# cyberspace-1-cpu-card.net
KiCad netlist of a schematic drawn in EAGLE
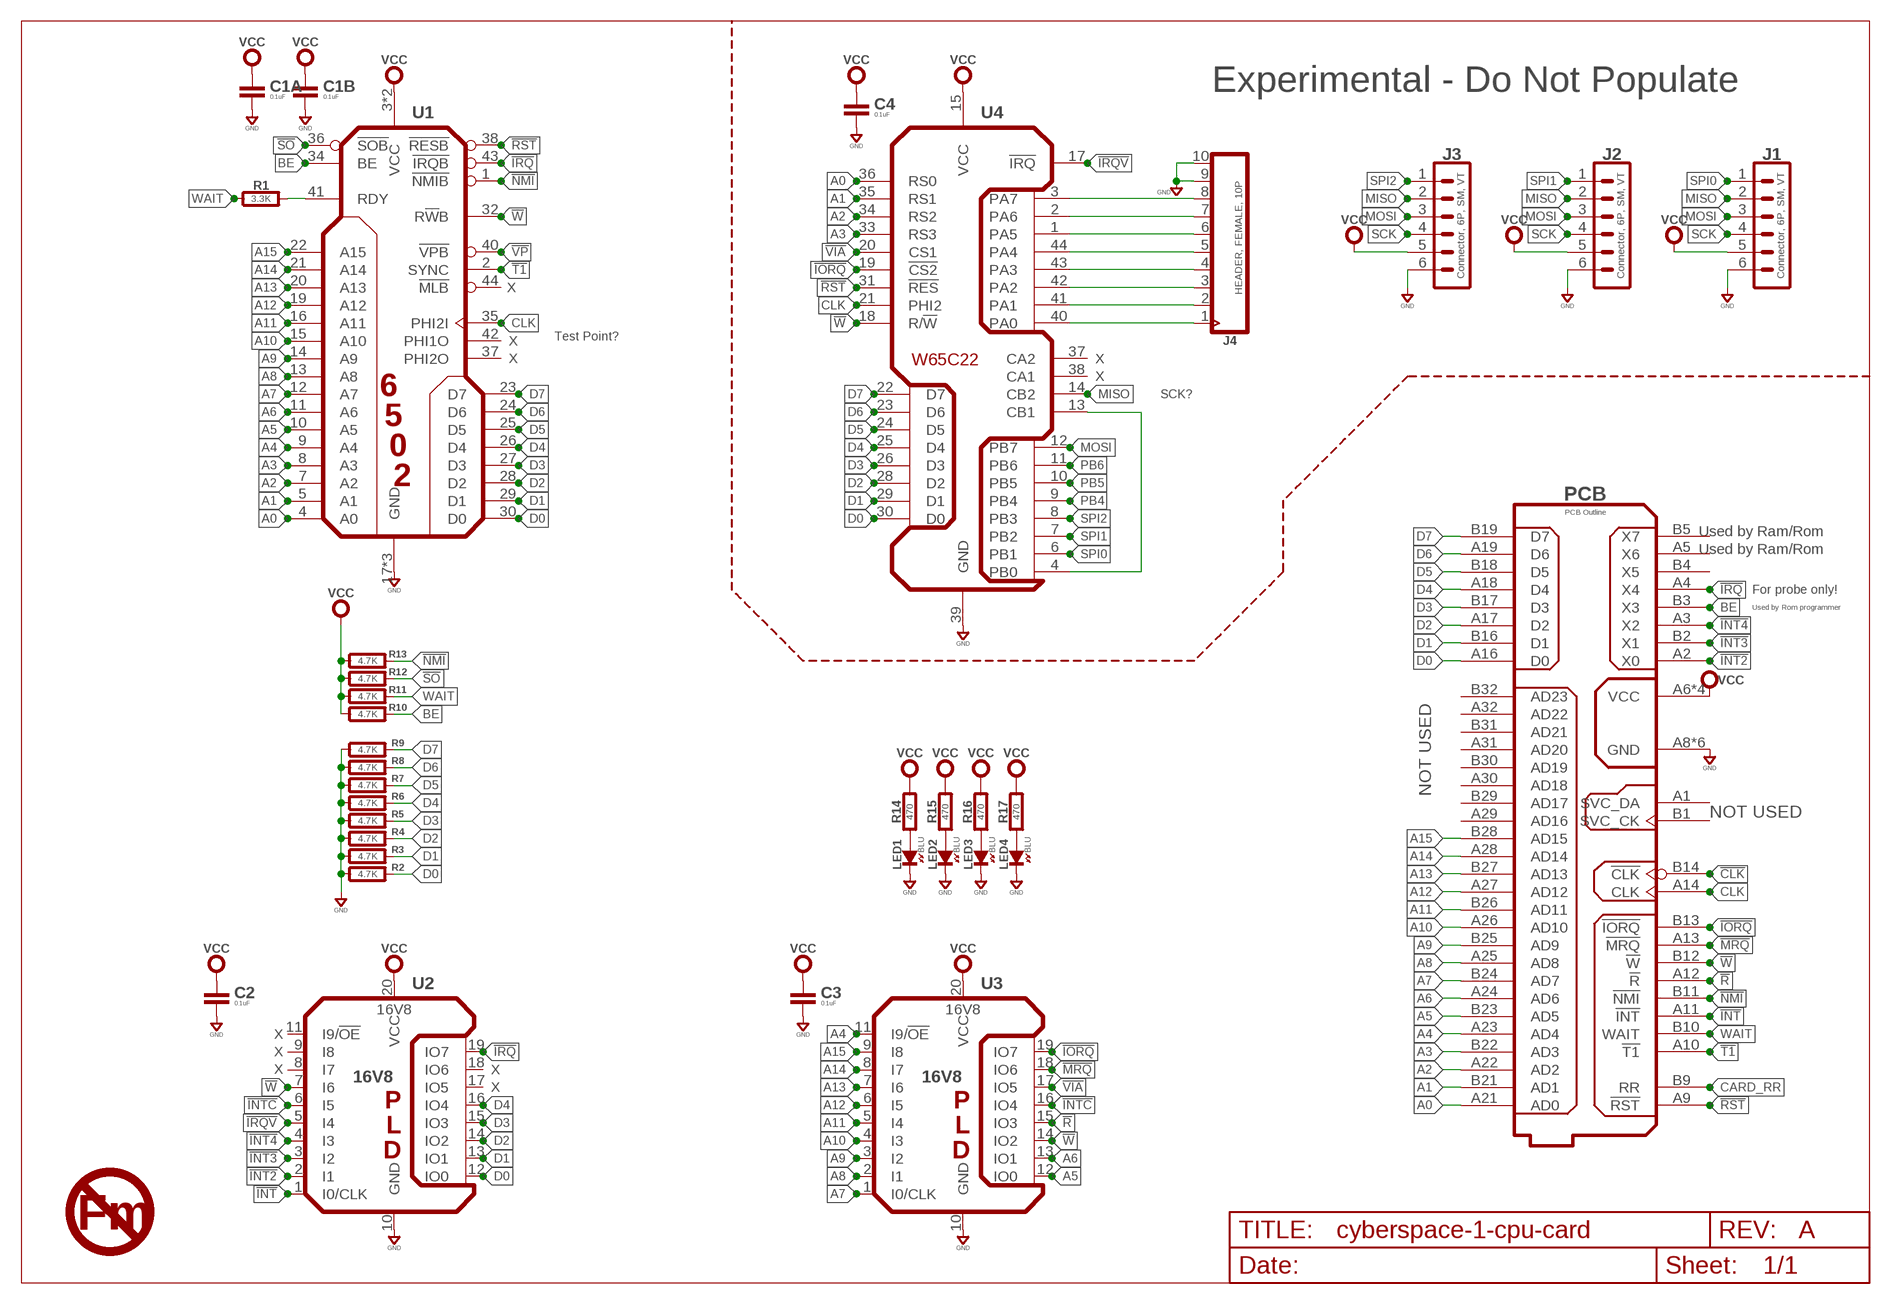
[diagram p0: schematic, sheet 1]

(export (version "E")
  (design (tool "Eeschema 10.0.6"))
  (components
    (comp (ref "C1A")
      (value "0.1uF")
      (footprint "eagle-import:0603-CAP")
      (libsource (lib "eagle-import") (part "CAPACITOR0603"))
    )
    (comp (ref "C1B")
      (value "0.1uF")
      (footprint "eagle-import:0603-CAP")
      (libsource (lib "eagle-import") (part "CAPACITOR0603"))
    )
    (comp (ref "C2")
      (value "0.1uF")
      (footprint "eagle-import:0603-CAP")
      (libsource (lib "eagle-import") (part "CAPACITOR0603"))
    )
    (comp (ref "C3")
      (value "0.1uF")
      (footprint "eagle-import:0603-CAP")
      (libsource (lib "eagle-import") (part "CAPACITOR0603"))
    )
    (comp (ref "C4")
      (value "0.1uF")
      (footprint "eagle-import:0603-CAP")
      (libsource (lib "eagle-import") (part "CAPACITOR0603"))
    )
    (comp (ref "J1")
      (value "Connector, 6P, SM, VT")
      (footprint "eagle-import:BM06B-SRSS-TB")
      (fields (field (name "MFR") "JST") (field (name "MPN") "BM06-SRSS-TB"))
      (libsource (lib "eagle-import") (part "06P-SM-VT-SMT"))
    )
    (comp (ref "J2")
      (value "Connector, 6P, SM, VT")
      (footprint "eagle-import:BM06B-SRSS-TB")
      (fields (field (name "MFR") "JST") (field (name "MPN") "BM06-SRSS-TB"))
      (libsource (lib "eagle-import") (part "06P-SM-VT-SMT"))
    )
    (comp (ref "J3")
      (value "Connector, 6P, SM, VT")
      (footprint "eagle-import:BM06B-SRSS-TB")
      (fields (field (name "MFR") "JST") (field (name "MPN") "BM06-SRSS-TB"))
      (libsource (lib "eagle-import") (part "06P-SM-VT-SMT"))
    )
    (comp (ref "J4")
      (value "HEADER, FEMALE, 10P")
      (footprint "eagle-import:H10-2.54")
      (fields (field (name "MFR") "Tayda") (field (name "MPN") "A-1306"))
      (libsource (lib "eagle-import") (part "CON_10X1-VT-THD-FEMALE"))
    )
    (comp (ref "LED1")
      (value "BLU")
      (footprint "eagle-import:SMD_0603")
      (libsource (lib "eagle-import") (part "SMT0603"))
    )
    (comp (ref "LED2")
      (value "BLU")
      (footprint "eagle-import:SMD_0603")
      (libsource (lib "eagle-import") (part "SMT0603"))
    )
    (comp (ref "LED3")
      (value "BLU")
      (footprint "eagle-import:SMD_0603")
      (libsource (lib "eagle-import") (part "SMT0603"))
    )
    (comp (ref "LED4")
      (value "BLU")
      (footprint "eagle-import:SMD_0603")
      (libsource (lib "eagle-import") (part "SMT0603"))
    )
    (comp (ref "PCB")
      (value "PCB Outline")
      (footprint "eagle-import:CYBERSPACE-CARD-TYPE-1A")
      (libsource (lib "eagle-import") (part "CYBERSPACE-1-CARD-1A"))
    )
    (comp (ref "R1")
      (value "3.3K")
      (footprint "eagle-import:0603-RES")
      (libsource (lib "eagle-import") (part "RESISTOR0603"))
    )
    (comp (ref "R2")
      (value "4.7K")
      (footprint "eagle-import:0603-RES")
      (libsource (lib "eagle-import") (part "RESISTOR0603"))
    )
    (comp (ref "R3")
      (value "4.7K")
      (footprint "eagle-import:0603-RES")
      (libsource (lib "eagle-import") (part "RESISTOR0603"))
    )
    (comp (ref "R4")
      (value "4.7K")
      (footprint "eagle-import:0603-RES")
      (libsource (lib "eagle-import") (part "RESISTOR0603"))
    )
    (comp (ref "R5")
      (value "4.7K")
      (footprint "eagle-import:0603-RES")
      (libsource (lib "eagle-import") (part "RESISTOR0603"))
    )
    (comp (ref "R6")
      (value "4.7K")
      (footprint "eagle-import:0603-RES")
      (libsource (lib "eagle-import") (part "RESISTOR0603"))
    )
    (comp (ref "R7")
      (value "4.7K")
      (footprint "eagle-import:0603-RES")
      (libsource (lib "eagle-import") (part "RESISTOR0603"))
    )
    (comp (ref "R8")
      (value "4.7K")
      (footprint "eagle-import:0603-RES")
      (libsource (lib "eagle-import") (part "RESISTOR0603"))
    )
    (comp (ref "R9")
      (value "4.7K")
      (footprint "eagle-import:0603-RES")
      (libsource (lib "eagle-import") (part "RESISTOR0603"))
    )
    (comp (ref "R10")
      (value "4.7K")
      (footprint "eagle-import:0603-RES")
      (libsource (lib "eagle-import") (part "RESISTOR0603"))
    )
    (comp (ref "R11")
      (value "4.7K")
      (footprint "eagle-import:0603-RES")
      (libsource (lib "eagle-import") (part "RESISTOR0603"))
    )
    (comp (ref "R12")
      (value "4.7K")
      (footprint "eagle-import:0603-RES")
      (libsource (lib "eagle-import") (part "RESISTOR0603"))
    )
    (comp (ref "R13")
      (value "4.7K")
      (footprint "eagle-import:0603-RES")
      (libsource (lib "eagle-import") (part "RESISTOR0603"))
    )
    (comp (ref "R14")
      (value "470")
      (footprint "eagle-import:0603-RES")
      (libsource (lib "eagle-import") (part "RESISTOR0603"))
    )
    (comp (ref "R15")
      (value "470")
      (footprint "eagle-import:0603-RES")
      (libsource (lib "eagle-import") (part "RESISTOR0603"))
    )
    (comp (ref "R16")
      (value "470")
      (footprint "eagle-import:0603-RES")
      (libsource (lib "eagle-import") (part "RESISTOR0603"))
    )
    (comp (ref "R17")
      (value "470")
      (footprint "eagle-import:0603-RES")
      (libsource (lib "eagle-import") (part "RESISTOR0603"))
    )
    (comp (ref "U$2")
      (value "NO-FERMIUM-5MM")
      (footprint "eagle-import:NO-FERMIUM-5MM")
      (libsource (lib "eagle-import") (part "NO-FERMIUM-5MM"))
    )
    (comp (ref "U1")
      (value "6502 Processor")
      (footprint "eagle-import:TQFP-44-10")
      (fields (field (name "MFR") "WDC") (field (name "MPN") "W65C02S6TQG-14"))
      (libsource (lib "eagle-import") (part "6502S?QC"))
    )
    (comp (ref "U2")
      (value "16V8")
      (footprint "eagle-import:SOP20")
      (fields (field (name "MFR") "Atmel") (field (name "MPN") "AF16V8B15SU"))
      (libsource (lib "eagle-import") (part "16V8-SOIC"))
    )
    (comp (ref "U3")
      (value "16V8")
      (footprint "eagle-import:SOP20")
      (fields (field (name "MFR") "Atmel") (field (name "MPN") "AF16V8B15SU"))
      (libsource (lib "eagle-import") (part "16V8-SOIC"))
    )
    (comp (ref "U4")
      (value "W65C22")
      (footprint "eagle-import:TQFP-44-10")
      (fields (field (name "MFR") "WDC") (field (name "MPN") "W65C22S6TQG-14"))
      (libsource (lib "eagle-import") (part "6522?QC"))
    )
  )
  (nets
    (net (code "1") (name "/~{CLK}") (class "Default")
      (node (ref "PCB") (pin "B14") (pinfunction "~{CLK}_B14") (pintype "bidirectional"))
    )
    (net (code "2") (name "/~{INT2}") (class "Default")
      (node (ref "PCB") (pin "A2") (pinfunction "X0_A2") (pintype "bidirectional"))
      (node (ref "U2") (pin "2") (pinfunction "I1_2") (pintype "bidirectional"))
    )
    (net (code "3") (name "/~{INT3}") (class "Default")
      (node (ref "PCB") (pin "B2") (pinfunction "X1_B2") (pintype "bidirectional"))
      (node (ref "U2") (pin "3") (pinfunction "I2_3") (pintype "bidirectional"))
    )
    (net (code "4") (name "/~{INT4}") (class "Default")
      (node (ref "PCB") (pin "A3") (pinfunction "X2_A3") (pintype "bidirectional"))
      (node (ref "U2") (pin "4") (pinfunction "I3_4") (pintype "bidirectional"))
    )
    (net (code "5") (name "/~{INTC}") (class "Default")
      (node (ref "U2") (pin "6") (pinfunction "I5_6") (pintype "bidirectional"))
      (node (ref "U3") (pin "16") (pinfunction "IO4_16") (pintype "bidirectional"))
    )
    (net (code "6") (name "/~{INT}") (class "Default")
      (node (ref "PCB") (pin "A11") (pinfunction "~{INT}_A11") (pintype "bidirectional"))
      (node (ref "U2") (pin "1") (pinfunction "I0/CLK_1") (pintype "bidirectional"))
    )
    (net (code "7") (name "/~{IORQ}") (class "Default")
      (node (ref "PCB") (pin "B13") (pinfunction "~{IORQ}_B13") (pintype "bidirectional"))
      (node (ref "U3") (pin "19") (pinfunction "IO7_19") (pintype "bidirectional"))
      (node (ref "U4") (pin "19") (pinfunction "~{CS2}_19") (pintype "input"))
    )
    (net (code "8") (name "/~{IRQV}") (class "Default")
      (node (ref "U2") (pin "5") (pinfunction "I4_5") (pintype "bidirectional"))
      (node (ref "U4") (pin "17") (pinfunction "~{IRQ}_17") (pintype "output"))
    )
    (net (code "9") (name "/~{IRQ}") (class "Default")
      (node (ref "PCB") (pin "A4") (pinfunction "X4_A4") (pintype "bidirectional"))
      (node (ref "U1") (pin "43") (pinfunction "~{IRQB}_43") (pintype "input"))
      (node (ref "U2") (pin "19") (pinfunction "IO7_19") (pintype "bidirectional"))
    )
    (net (code "10") (name "/~{MRQ}") (class "Default")
      (node (ref "PCB") (pin "A13") (pinfunction "~{MRQ}_A13") (pintype "bidirectional"))
      (node (ref "U3") (pin "18") (pinfunction "IO6_18") (pintype "bidirectional"))
    )
    (net (code "11") (name "/~{NMI}") (class "Default")
      (node (ref "PCB") (pin "B11") (pinfunction "~{NMI}_B11") (pintype "bidirectional"))
      (node (ref "R13") (pin "2") (pinfunction "2_2") (pintype "passive"))
      (node (ref "U1") (pin "1") (pinfunction "~{NMIB}_1") (pintype "input"))
    )
    (net (code "12") (name "/~{RST}") (class "Default")
      (node (ref "PCB") (pin "A9") (pinfunction "~{RST}_A9") (pintype "bidirectional"))
      (node (ref "U1") (pin "38") (pinfunction "~{RESB}_38") (pintype "input"))
      (node (ref "U4") (pin "31") (pinfunction "~{RES}_31") (pintype "input"))
    )
    (net (code "13") (name "/~{R}") (class "Default")
      (node (ref "PCB") (pin "A12") (pinfunction "~{R}_A12") (pintype "bidirectional"))
      (node (ref "U3") (pin "15") (pinfunction "IO3_15") (pintype "bidirectional"))
    )
    (net (code "14") (name "/~{SO}") (class "Default")
      (node (ref "R12") (pin "2") (pinfunction "2_2") (pintype "passive"))
      (node (ref "U1") (pin "36") (pinfunction "~{SOB}_36") (pintype "input"))
    )
    (net (code "15") (name "/~{T1}") (class "Default")
      (node (ref "PCB") (pin "A10") (pinfunction "~{T1}_A10") (pintype "bidirectional"))
      (node (ref "U1") (pin "2") (pinfunction "SYNC_2") (pintype "output"))
    )
    (net (code "16") (name "/~{VIA}") (class "Default")
      (node (ref "U3") (pin "17") (pinfunction "IO5_17") (pintype "bidirectional"))
      (node (ref "U4") (pin "20") (pinfunction "CS1_20") (pintype "input"))
    )
    (net (code "17") (name "/~{VP}") (class "Default")
      (node (ref "U1") (pin "40") (pinfunction "~{VPB}_40") (pintype "output"))
    )
    (net (code "18") (name "/~{W}") (class "Default")
      (node (ref "PCB") (pin "B12") (pinfunction "~{W}_B12") (pintype "bidirectional"))
      (node (ref "U1") (pin "32") (pinfunction "R~{W}B_32") (pintype "output"))
      (node (ref "U2") (pin "7") (pinfunction "I6_7") (pintype "bidirectional"))
      (node (ref "U3") (pin "14") (pinfunction "IO2_14") (pintype "bidirectional"))
      (node (ref "U4") (pin "18") (pinfunction "R/~{W}_18") (pintype "input"))
    )
    (net (code "19") (name "A0") (class "Default")
      (node (ref "PCB") (pin "A21") (pinfunction "AD0_A21") (pintype "bidirectional"))
      (node (ref "U1") (pin "4") (pinfunction "A0_4") (pintype "output"))
      (node (ref "U4") (pin "36") (pinfunction "RS0_36") (pintype "input"))
    )
    (net (code "20") (name "A1") (class "Default")
      (node (ref "PCB") (pin "B21") (pinfunction "AD1_B21") (pintype "bidirectional"))
      (node (ref "U1") (pin "5") (pinfunction "A1_5") (pintype "output"))
      (node (ref "U4") (pin "35") (pinfunction "RS1_35") (pintype "input"))
    )
    (net (code "21") (name "A2") (class "Default")
      (node (ref "PCB") (pin "A22") (pinfunction "AD2_A22") (pintype "bidirectional"))
      (node (ref "U1") (pin "7") (pinfunction "A2_7") (pintype "output"))
      (node (ref "U4") (pin "34") (pinfunction "RS2_34") (pintype "input"))
    )
    (net (code "22") (name "A3") (class "Default")
      (node (ref "PCB") (pin "B22") (pinfunction "AD3_B22") (pintype "bidirectional"))
      (node (ref "U1") (pin "8") (pinfunction "A3_8") (pintype "output"))
      (node (ref "U4") (pin "33") (pinfunction "RS3_33") (pintype "input"))
    )
    (net (code "23") (name "A4") (class "Default")
      (node (ref "PCB") (pin "A23") (pinfunction "AD4_A23") (pintype "bidirectional"))
      (node (ref "U1") (pin "9") (pinfunction "A4_9") (pintype "output"))
      (node (ref "U3") (pin "11") (pinfunction "I9/~{OE}_11") (pintype "bidirectional"))
    )
    (net (code "24") (name "A5") (class "Default")
      (node (ref "PCB") (pin "B23") (pinfunction "AD5_B23") (pintype "bidirectional"))
      (node (ref "U1") (pin "10") (pinfunction "A5_10") (pintype "output"))
      (node (ref "U3") (pin "12") (pinfunction "IO0_12") (pintype "bidirectional"))
    )
    (net (code "25") (name "A6") (class "Default")
      (node (ref "PCB") (pin "A24") (pinfunction "AD6_A24") (pintype "bidirectional"))
      (node (ref "U1") (pin "11") (pinfunction "A6_11") (pintype "output"))
      (node (ref "U3") (pin "13") (pinfunction "IO1_13") (pintype "bidirectional"))
    )
    (net (code "26") (name "A7") (class "Default")
      (node (ref "PCB") (pin "B24") (pinfunction "AD7_B24") (pintype "bidirectional"))
      (node (ref "U1") (pin "12") (pinfunction "A7_12") (pintype "output"))
      (node (ref "U3") (pin "1") (pinfunction "I0/CLK_1") (pintype "bidirectional"))
    )
    (net (code "27") (name "A8") (class "Default")
      (node (ref "PCB") (pin "A25") (pinfunction "AD8_A25") (pintype "bidirectional"))
      (node (ref "U1") (pin "13") (pinfunction "A8_13") (pintype "output"))
      (node (ref "U3") (pin "2") (pinfunction "I1_2") (pintype "bidirectional"))
    )
    (net (code "28") (name "A9") (class "Default")
      (node (ref "PCB") (pin "B25") (pinfunction "AD9_B25") (pintype "bidirectional"))
      (node (ref "U1") (pin "14") (pinfunction "A9_14") (pintype "output"))
      (node (ref "U3") (pin "3") (pinfunction "I2_3") (pintype "bidirectional"))
    )
    (net (code "29") (name "A10") (class "Default")
      (node (ref "PCB") (pin "A26") (pinfunction "AD10_A26") (pintype "bidirectional"))
      (node (ref "U1") (pin "15") (pinfunction "A10_15") (pintype "output"))
      (node (ref "U3") (pin "4") (pinfunction "I3_4") (pintype "bidirectional"))
    )
    (net (code "30") (name "A11") (class "Default")
      (node (ref "PCB") (pin "B26") (pinfunction "AD11_B26") (pintype "bidirectional"))
      (node (ref "U1") (pin "16") (pinfunction "A11_16") (pintype "output"))
      (node (ref "U3") (pin "5") (pinfunction "I4_5") (pintype "bidirectional"))
    )
    (net (code "31") (name "A12") (class "Default")
      (node (ref "PCB") (pin "A27") (pinfunction "AD12_A27") (pintype "bidirectional"))
      (node (ref "U1") (pin "19") (pinfunction "A12_19") (pintype "output"))
      (node (ref "U3") (pin "6") (pinfunction "I5_6") (pintype "bidirectional"))
    )
    (net (code "32") (name "A13") (class "Default")
      (node (ref "PCB") (pin "B27") (pinfunction "AD13_B27") (pintype "bidirectional"))
      (node (ref "U1") (pin "20") (pinfunction "A13_20") (pintype "output"))
      (node (ref "U3") (pin "7") (pinfunction "I6_7") (pintype "bidirectional"))
    )
    (net (code "33") (name "A14") (class "Default")
      (node (ref "PCB") (pin "A28") (pinfunction "AD14_A28") (pintype "bidirectional"))
      (node (ref "U1") (pin "21") (pinfunction "A14_21") (pintype "output"))
      (node (ref "U3") (pin "8") (pinfunction "I7_8") (pintype "bidirectional"))
    )
    (net (code "34") (name "A15") (class "Default")
      (node (ref "PCB") (pin "B28") (pinfunction "AD15_B28") (pintype "bidirectional"))
      (node (ref "U1") (pin "22") (pinfunction "A15_22") (pintype "output"))
      (node (ref "U3") (pin "9") (pinfunction "I8_9") (pintype "bidirectional"))
    )
    (net (code "35") (name "BE") (class "Default")
      (node (ref "PCB") (pin "B3") (pinfunction "X3_B3") (pintype "bidirectional"))
      (node (ref "R10") (pin "2") (pinfunction "2_2") (pintype "passive"))
      (node (ref "U1") (pin "34") (pinfunction "BE_34") (pintype "input"))
    )
    (net (code "36") (name "CARD_RR") (class "Default")
      (node (ref "PCB") (pin "B9") (pinfunction "RR_B9") (pintype "bidirectional"))
    )
    (net (code "37") (name "CLK") (class "Default")
      (node (ref "PCB") (pin "A14") (pinfunction "CLK_A14") (pintype "bidirectional"))
      (node (ref "U1") (pin "35") (pinfunction "PHI2I_35") (pintype "input"))
      (node (ref "U4") (pin "21") (pinfunction "PHI2_21") (pintype "input"))
    )
    (net (code "38") (name "D0") (class "Default")
      (node (ref "PCB") (pin "A16") (pinfunction "D0_A16") (pintype "bidirectional"))
      (node (ref "R2") (pin "2") (pinfunction "2_2") (pintype "passive"))
      (node (ref "U1") (pin "30") (pinfunction "D0_30") (pintype "bidirectional"))
      (node (ref "U2") (pin "12") (pinfunction "IO0_12") (pintype "bidirectional"))
      (node (ref "U4") (pin "30") (pinfunction "D0_30") (pintype "bidirectional"))
    )
    (net (code "39") (name "D1") (class "Default")
      (node (ref "PCB") (pin "B16") (pinfunction "D1_B16") (pintype "bidirectional"))
      (node (ref "R3") (pin "2") (pinfunction "2_2") (pintype "passive"))
      (node (ref "U1") (pin "29") (pinfunction "D1_29") (pintype "bidirectional"))
      (node (ref "U2") (pin "13") (pinfunction "IO1_13") (pintype "bidirectional"))
      (node (ref "U4") (pin "29") (pinfunction "D1_29") (pintype "bidirectional"))
    )
    (net (code "40") (name "D2") (class "Default")
      (node (ref "PCB") (pin "A17") (pinfunction "D2_A17") (pintype "bidirectional"))
      (node (ref "R4") (pin "2") (pinfunction "2_2") (pintype "passive"))
      (node (ref "U1") (pin "28") (pinfunction "D2_28") (pintype "bidirectional"))
      (node (ref "U2") (pin "14") (pinfunction "IO2_14") (pintype "bidirectional"))
      (node (ref "U4") (pin "28") (pinfunction "D2_28") (pintype "bidirectional"))
    )
    (net (code "41") (name "D3") (class "Default")
      (node (ref "PCB") (pin "B17") (pinfunction "D3_B17") (pintype "bidirectional"))
      (node (ref "R5") (pin "2") (pinfunction "2_2") (pintype "passive"))
      (node (ref "U1") (pin "27") (pinfunction "D3_27") (pintype "bidirectional"))
      (node (ref "U2") (pin "15") (pinfunction "IO3_15") (pintype "bidirectional"))
      (node (ref "U4") (pin "26") (pinfunction "D3_26") (pintype "bidirectional"))
    )
    (net (code "42") (name "D4") (class "Default")
      (node (ref "PCB") (pin "A18") (pinfunction "D4_A18") (pintype "bidirectional"))
      (node (ref "R6") (pin "2") (pinfunction "2_2") (pintype "passive"))
      (node (ref "U1") (pin "26") (pinfunction "D4_26") (pintype "bidirectional"))
      (node (ref "U2") (pin "16") (pinfunction "IO4_16") (pintype "bidirectional"))
      (node (ref "U4") (pin "25") (pinfunction "D4_25") (pintype "bidirectional"))
    )
    (net (code "43") (name "D5") (class "Default")
      (node (ref "PCB") (pin "B18") (pinfunction "D5_B18") (pintype "bidirectional"))
      (node (ref "R7") (pin "2") (pinfunction "2_2") (pintype "passive"))
      (node (ref "U1") (pin "25") (pinfunction "D5_25") (pintype "bidirectional"))
      (node (ref "U4") (pin "24") (pinfunction "D5_24") (pintype "bidirectional"))
    )
    (net (code "44") (name "D6") (class "Default")
      (node (ref "PCB") (pin "A19") (pinfunction "D6_A19") (pintype "bidirectional"))
      (node (ref "R8") (pin "2") (pinfunction "2_2") (pintype "passive"))
      (node (ref "U1") (pin "24") (pinfunction "D6_24") (pintype "bidirectional"))
      (node (ref "U4") (pin "23") (pinfunction "D6_23") (pintype "bidirectional"))
    )
    (net (code "45") (name "D7") (class "Default")
      (node (ref "PCB") (pin "B19") (pinfunction "D7_B19") (pintype "bidirectional"))
      (node (ref "R9") (pin "2") (pinfunction "2_2") (pintype "passive"))
      (node (ref "U1") (pin "23") (pinfunction "D7_23") (pintype "bidirectional"))
      (node (ref "U4") (pin "22") (pinfunction "D7_22") (pintype "bidirectional"))
    )
    (net (code "46") (name "GND") (class "Default")
      (node (ref "C1A") (pin "2") (pinfunction "2_2") (pintype "passive"))
      (node (ref "C1B") (pin "2") (pinfunction "2_2") (pintype "passive"))
      (node (ref "C2") (pin "2") (pinfunction "2_2") (pintype "passive"))
      (node (ref "C3") (pin "2") (pinfunction "2_2") (pintype "passive"))
      (node (ref "C4") (pin "2") (pinfunction "2_2") (pintype "passive"))
      (node (ref "J1") (pin "6") (pinfunction "6_6") (pintype "passive"))
      (node (ref "J2") (pin "6") (pinfunction "6_6") (pintype "passive"))
      (node (ref "J3") (pin "6") (pinfunction "6_6") (pintype "passive"))
      (node (ref "J4") (pin "10") (pinfunction "10_10") (pintype "bidirectional"))
      (node (ref "J4") (pin "9") (pinfunction "9_9") (pintype "bidirectional"))
      (node (ref "LED1") (pin "K") (pinfunction "C_K") (pintype "passive"))
      (node (ref "LED2") (pin "K") (pinfunction "C_K") (pintype "passive"))
      (node (ref "LED3") (pin "K") (pinfunction "C_K") (pintype "passive"))
      (node (ref "LED4") (pin "K") (pinfunction "C_K") (pintype "passive"))
      (node (ref "PCB") (pin "A15") (pinfunction "GND_A15") (pintype "power_in"))
      (node (ref "PCB") (pin "A20") (pinfunction "GND_A20") (pintype "power_in"))
      (node (ref "PCB") (pin "A8") (pinfunction "GND_A8") (pintype "power_in"))
      (node (ref "PCB") (pin "B15") (pinfunction "GND_B15") (pintype "power_in"))
      (node (ref "PCB") (pin "B20") (pinfunction "GND_B20") (pintype "power_in"))
      (node (ref "PCB") (pin "B8") (pinfunction "GND_B8") (pintype "power_in"))
      (node (ref "R2") (pin "1") (pinfunction "1_1") (pintype "passive"))
      (node (ref "R3") (pin "1") (pinfunction "1_1") (pintype "passive"))
      (node (ref "R4") (pin "1") (pinfunction "1_1") (pintype "passive"))
      (node (ref "R5") (pin "1") (pinfunction "1_1") (pintype "passive"))
      (node (ref "R6") (pin "1") (pinfunction "1_1") (pintype "passive"))
      (node (ref "R7") (pin "1") (pinfunction "1_1") (pintype "passive"))
      (node (ref "R8") (pin "1") (pinfunction "1_1") (pintype "passive"))
      (node (ref "R9") (pin "1") (pinfunction "1_1") (pintype "passive"))
      (node (ref "U1") (pin "17") (pinfunction "GND_17") (pintype "power_in"))
      (node (ref "U1") (pin "18") (pinfunction "GND_18") (pintype "power_in"))
      (node (ref "U1") (pin "39") (pinfunction "GND_39") (pintype "power_in"))
      (node (ref "U2") (pin "10") (pinfunction "GND_10") (pintype "bidirectional"))
      (node (ref "U3") (pin "10") (pinfunction "GND_10") (pintype "bidirectional"))
      (node (ref "U4") (pin "39") (pinfunction "GND_39") (pintype "power_in"))
    )
    (net (code "47") (name "MISO") (class "Default")
      (node (ref "J1") (pin "2") (pinfunction "2_2") (pintype "passive"))
      (node (ref "J2") (pin "2") (pinfunction "2_2") (pintype "passive"))
      (node (ref "J3") (pin "2") (pinfunction "2_2") (pintype "passive"))
      (node (ref "U4") (pin "14") (pinfunction "CB2_14") (pintype "bidirectional"))
    )
    (net (code "48") (name "MOSI") (class "Default")
      (node (ref "J1") (pin "3") (pinfunction "3_3") (pintype "passive"))
      (node (ref "J2") (pin "3") (pinfunction "3_3") (pintype "passive"))
      (node (ref "J3") (pin "3") (pinfunction "3_3") (pintype "passive"))
      (node (ref "U4") (pin "12") (pinfunction "PB7_12") (pintype "bidirectional"))
    )
    (net (code "49") (name "Net-(LED1-PadA)") (class "Default")
      (node (ref "LED1") (pin "A") (pinfunction "A_A") (pintype "passive"))
      (node (ref "R14") (pin "1") (pinfunction "1_1") (pintype "passive"))
    )
    (net (code "50") (name "Net-(LED2-PadA)") (class "Default")
      (node (ref "LED2") (pin "A") (pinfunction "A_A") (pintype "passive"))
      (node (ref "R15") (pin "1") (pinfunction "1_1") (pintype "passive"))
    )
    (net (code "51") (name "Net-(LED3-PadA)") (class "Default")
      (node (ref "LED3") (pin "A") (pinfunction "A_A") (pintype "passive"))
      (node (ref "R16") (pin "1") (pinfunction "1_1") (pintype "passive"))
    )
    (net (code "52") (name "Net-(LED4-PadA)") (class "Default")
      (node (ref "LED4") (pin "A") (pinfunction "A_A") (pintype "passive"))
      (node (ref "R17") (pin "1") (pinfunction "1_1") (pintype "passive"))
    )
    (net (code "53") (name "Net-(U1-RDY)") (class "Default")
      (node (ref "R1") (pin "2") (pinfunction "2_2") (pintype "passive"))
      (node (ref "U1") (pin "41") (pinfunction "RDY_41") (pintype "input"))
    )
    (net (code "54") (name "Net-(U4-CB1)") (class "Default")
      (node (ref "U4") (pin "13") (pinfunction "CB1_13") (pintype "bidirectional"))
      (node (ref "U4") (pin "4") (pinfunction "PB0_4") (pintype "bidirectional"))
    )
    (net (code "55") (name "Net-(U4-PA0)") (class "Default")
      (node (ref "J4") (pin "1") (pinfunction "1_1") (pintype "bidirectional"))
      (node (ref "U4") (pin "40") (pinfunction "PA0_40") (pintype "bidirectional"))
    )
    (net (code "56") (name "Net-(U4-PA1)") (class "Default")
      (node (ref "J4") (pin "2") (pinfunction "2_2") (pintype "bidirectional"))
      (node (ref "U4") (pin "41") (pinfunction "PA1_41") (pintype "bidirectional"))
    )
    (net (code "57") (name "Net-(U4-PA2)") (class "Default")
      (node (ref "J4") (pin "3") (pinfunction "3_3") (pintype "bidirectional"))
      (node (ref "U4") (pin "42") (pinfunction "PA2_42") (pintype "bidirectional"))
    )
    (net (code "58") (name "Net-(U4-PA3)") (class "Default")
      (node (ref "J4") (pin "4") (pinfunction "4_4") (pintype "bidirectional"))
      (node (ref "U4") (pin "43") (pinfunction "PA3_43") (pintype "bidirectional"))
    )
    (net (code "59") (name "Net-(U4-PA4)") (class "Default")
      (node (ref "J4") (pin "5") (pinfunction "5_5") (pintype "bidirectional"))
      (node (ref "U4") (pin "44") (pinfunction "PA4_44") (pintype "bidirectional"))
    )
    (net (code "60") (name "Net-(U4-PA5)") (class "Default")
      (node (ref "J4") (pin "6") (pinfunction "6_6") (pintype "bidirectional"))
      (node (ref "U4") (pin "1") (pinfunction "PA5_1") (pintype "bidirectional"))
    )
    (net (code "61") (name "Net-(U4-PA6)") (class "Default")
      (node (ref "J4") (pin "7") (pinfunction "7_7") (pintype "bidirectional"))
      (node (ref "U4") (pin "2") (pinfunction "PA6_2") (pintype "bidirectional"))
    )
    (net (code "62") (name "Net-(U4-PA7)") (class "Default")
      (node (ref "J4") (pin "8") (pinfunction "8_8") (pintype "bidirectional"))
      (node (ref "U4") (pin "3") (pinfunction "PA7_3") (pintype "bidirectional"))
    )
    (net (code "63") (name "PB4") (class "Default")
      (node (ref "U4") (pin "9") (pinfunction "PB4_9") (pintype "bidirectional"))
    )
    (net (code "64") (name "PB5") (class "Default")
      (node (ref "U4") (pin "10") (pinfunction "PB5_10") (pintype "bidirectional"))
    )
    (net (code "65") (name "PB6") (class "Default")
      (node (ref "U4") (pin "11") (pinfunction "PB6_11") (pintype "bidirectional"))
    )
    (net (code "66") (name "SCK") (class "Default")
      (node (ref "J1") (pin "4") (pinfunction "4_4") (pintype "passive"))
      (node (ref "J2") (pin "4") (pinfunction "4_4") (pintype "passive"))
      (node (ref "J3") (pin "4") (pinfunction "4_4") (pintype "passive"))
    )
    (net (code "67") (name "SPI0") (class "Default")
      (node (ref "J1") (pin "1") (pinfunction "1_1") (pintype "passive"))
      (node (ref "U4") (pin "6") (pinfunction "PB1_6") (pintype "bidirectional"))
    )
    (net (code "68") (name "SPI1") (class "Default")
      (node (ref "J2") (pin "1") (pinfunction "1_1") (pintype "passive"))
      (node (ref "U4") (pin "7") (pinfunction "PB2_7") (pintype "bidirectional"))
    )
    (net (code "69") (name "SPI2") (class "Default")
      (node (ref "J3") (pin "1") (pinfunction "1_1") (pintype "passive"))
      (node (ref "U4") (pin "8") (pinfunction "PB3_8") (pintype "bidirectional"))
    )
    (net (code "70") (name "VCC") (class "Default")
      (node (ref "C1A") (pin "1") (pinfunction "1_1") (pintype "passive"))
      (node (ref "C1B") (pin "1") (pinfunction "1_1") (pintype "passive"))
      (node (ref "C2") (pin "1") (pinfunction "1_1") (pintype "passive"))
      (node (ref "C3") (pin "1") (pinfunction "1_1") (pintype "passive"))
      (node (ref "C4") (pin "1") (pinfunction "1_1") (pintype "passive"))
      (node (ref "J1") (pin "5") (pinfunction "5_5") (pintype "passive"))
      (node (ref "J2") (pin "5") (pinfunction "5_5") (pintype "passive"))
      (node (ref "J3") (pin "5") (pinfunction "5_5") (pintype "passive"))
      (node (ref "PCB") (pin "A6") (pinfunction "VCC_A6") (pintype "power_in"))
      (node (ref "PCB") (pin "A7") (pinfunction "VCC_A7") (pintype "power_in"))
      (node (ref "PCB") (pin "B6") (pinfunction "VCC_B6") (pintype "power_in"))
      (node (ref "PCB") (pin "B7") (pinfunction "VCC_B7") (pintype "power_in"))
      (node (ref "R10") (pin "1") (pinfunction "1_1") (pintype "passive"))
      (node (ref "R11") (pin "1") (pinfunction "1_1") (pintype "passive"))
      (node (ref "R12") (pin "1") (pinfunction "1_1") (pintype "passive"))
      (node (ref "R13") (pin "1") (pinfunction "1_1") (pintype "passive"))
      (node (ref "R14") (pin "2") (pinfunction "2_2") (pintype "passive"))
      (node (ref "R15") (pin "2") (pinfunction "2_2") (pintype "passive"))
      (node (ref "R16") (pin "2") (pinfunction "2_2") (pintype "passive"))
      (node (ref "R17") (pin "2") (pinfunction "2_2") (pintype "passive"))
      (node (ref "U1") (pin "3") (pinfunction "VCC_3") (pintype "power_in"))
      (node (ref "U1") (pin "31") (pinfunction "VCC_31") (pintype "power_in"))
      (node (ref "U2") (pin "20") (pinfunction "VCC_20") (pintype "bidirectional"))
      (node (ref "U3") (pin "20") (pinfunction "VCC_20") (pintype "bidirectional"))
      (node (ref "U4") (pin "15") (pinfunction "VCC_15") (pintype "power_in"))
    )
    (net (code "71") (name "WAIT") (class "Default")
      (node (ref "PCB") (pin "B10") (pinfunction "WAIT_B10") (pintype "bidirectional"))
      (node (ref "R1") (pin "1") (pinfunction "1_1") (pintype "passive"))
      (node (ref "R11") (pin "2") (pinfunction "2_2") (pintype "passive"))
    )
    (net (code "72") (name "unconnected-(PCB-AD16-PadA29)") (class "Default")
      (node (ref "PCB") (pin "A29") (pinfunction "AD16_A29") (pintype "bidirectional"))
    )
    (net (code "73") (name "unconnected-(PCB-AD17-PadB29)") (class "Default")
      (node (ref "PCB") (pin "B29") (pinfunction "AD17_B29") (pintype "bidirectional"))
    )
    (net (code "74") (name "unconnected-(PCB-AD18-PadA30)") (class "Default")
      (node (ref "PCB") (pin "A30") (pinfunction "AD18_A30") (pintype "bidirectional"))
    )
    (net (code "75") (name "unconnected-(PCB-AD19-PadB30)") (class "Default")
      (node (ref "PCB") (pin "B30") (pinfunction "AD19_B30") (pintype "bidirectional"))
    )
    (net (code "76") (name "unconnected-(PCB-AD20-PadA31)") (class "Default")
      (node (ref "PCB") (pin "A31") (pinfunction "AD20_A31") (pintype "bidirectional"))
    )
    (net (code "77") (name "unconnected-(PCB-AD21-PadB31)") (class "Default")
      (node (ref "PCB") (pin "B31") (pinfunction "AD21_B31") (pintype "bidirectional"))
    )
    (net (code "78") (name "unconnected-(PCB-AD22-PadA32)") (class "Default")
      (node (ref "PCB") (pin "A32") (pinfunction "AD22_A32") (pintype "bidirectional"))
    )
    (net (code "79") (name "unconnected-(PCB-AD23-PadB32)") (class "Default")
      (node (ref "PCB") (pin "B32") (pinfunction "AD23_B32") (pintype "bidirectional"))
    )
    (net (code "80") (name "unconnected-(PCB-SVC_CK-PadB1)") (class "Default")
      (node (ref "PCB") (pin "B1") (pinfunction "SVC_CK_B1") (pintype "bidirectional"))
    )
    (net (code "81") (name "unconnected-(PCB-SVC_DA-PadA1)") (class "Default")
      (node (ref "PCB") (pin "A1") (pinfunction "SVC_DA_A1") (pintype "bidirectional"))
    )
    (net (code "82") (name "unconnected-(PCB-X5-PadB4)") (class "Default")
      (node (ref "PCB") (pin "B4") (pinfunction "X5_B4") (pintype "bidirectional"))
    )
    (net (code "83") (name "unconnected-(PCB-X6-PadA5)") (class "Default")
      (node (ref "PCB") (pin "A5") (pinfunction "X6_A5") (pintype "bidirectional"))
    )
    (net (code "84") (name "unconnected-(PCB-X7-PadB5)") (class "Default")
      (node (ref "PCB") (pin "B5") (pinfunction "X7_B5") (pintype "bidirectional"))
    )
    (net (code "85") (name "unconnected-(U1-PHI1O-Pad42)") (class "Default")
      (node (ref "U1") (pin "42") (pinfunction "PHI1O_42") (pintype "output"))
    )
    (net (code "86") (name "unconnected-(U1-PHI2O-Pad37)") (class "Default")
      (node (ref "U1") (pin "37") (pinfunction "PHI2O_37") (pintype "output"))
    )
    (net (code "87") (name "unconnected-(U1-~{MLB}-Pad44)") (class "Default")
      (node (ref "U1") (pin "44") (pinfunction "~{MLB}_44") (pintype "output"))
    )
    (net (code "88") (name "unconnected-(U2-I7-Pad8)") (class "Default")
      (node (ref "U2") (pin "8") (pinfunction "I7_8") (pintype "bidirectional"))
    )
    (net (code "89") (name "unconnected-(U2-I8-Pad9)") (class "Default")
      (node (ref "U2") (pin "9") (pinfunction "I8_9") (pintype "bidirectional"))
    )
    (net (code "90") (name "unconnected-(U2-I9{slash}~{OE}-Pad11)") (class "Default")
      (node (ref "U2") (pin "11") (pinfunction "I9/~{OE}_11") (pintype "bidirectional"))
    )
    (net (code "91") (name "unconnected-(U2-IO5-Pad17)") (class "Default")
      (node (ref "U2") (pin "17") (pinfunction "IO5_17") (pintype "bidirectional"))
    )
    (net (code "92") (name "unconnected-(U2-IO6-Pad18)") (class "Default")
      (node (ref "U2") (pin "18") (pinfunction "IO6_18") (pintype "bidirectional"))
    )
    (net (code "93") (name "unconnected-(U4-CA1-Pad38)") (class "Default")
      (node (ref "U4") (pin "38") (pinfunction "CA1_38") (pintype "input"))
    )
    (net (code "94") (name "unconnected-(U4-CA2-Pad37)") (class "Default")
      (node (ref "U4") (pin "37") (pinfunction "CA2_37") (pintype "bidirectional"))
    )
  )
)
